# InterlockAdapter.net
KiCad netlist of a schematic drawn in EAGLE
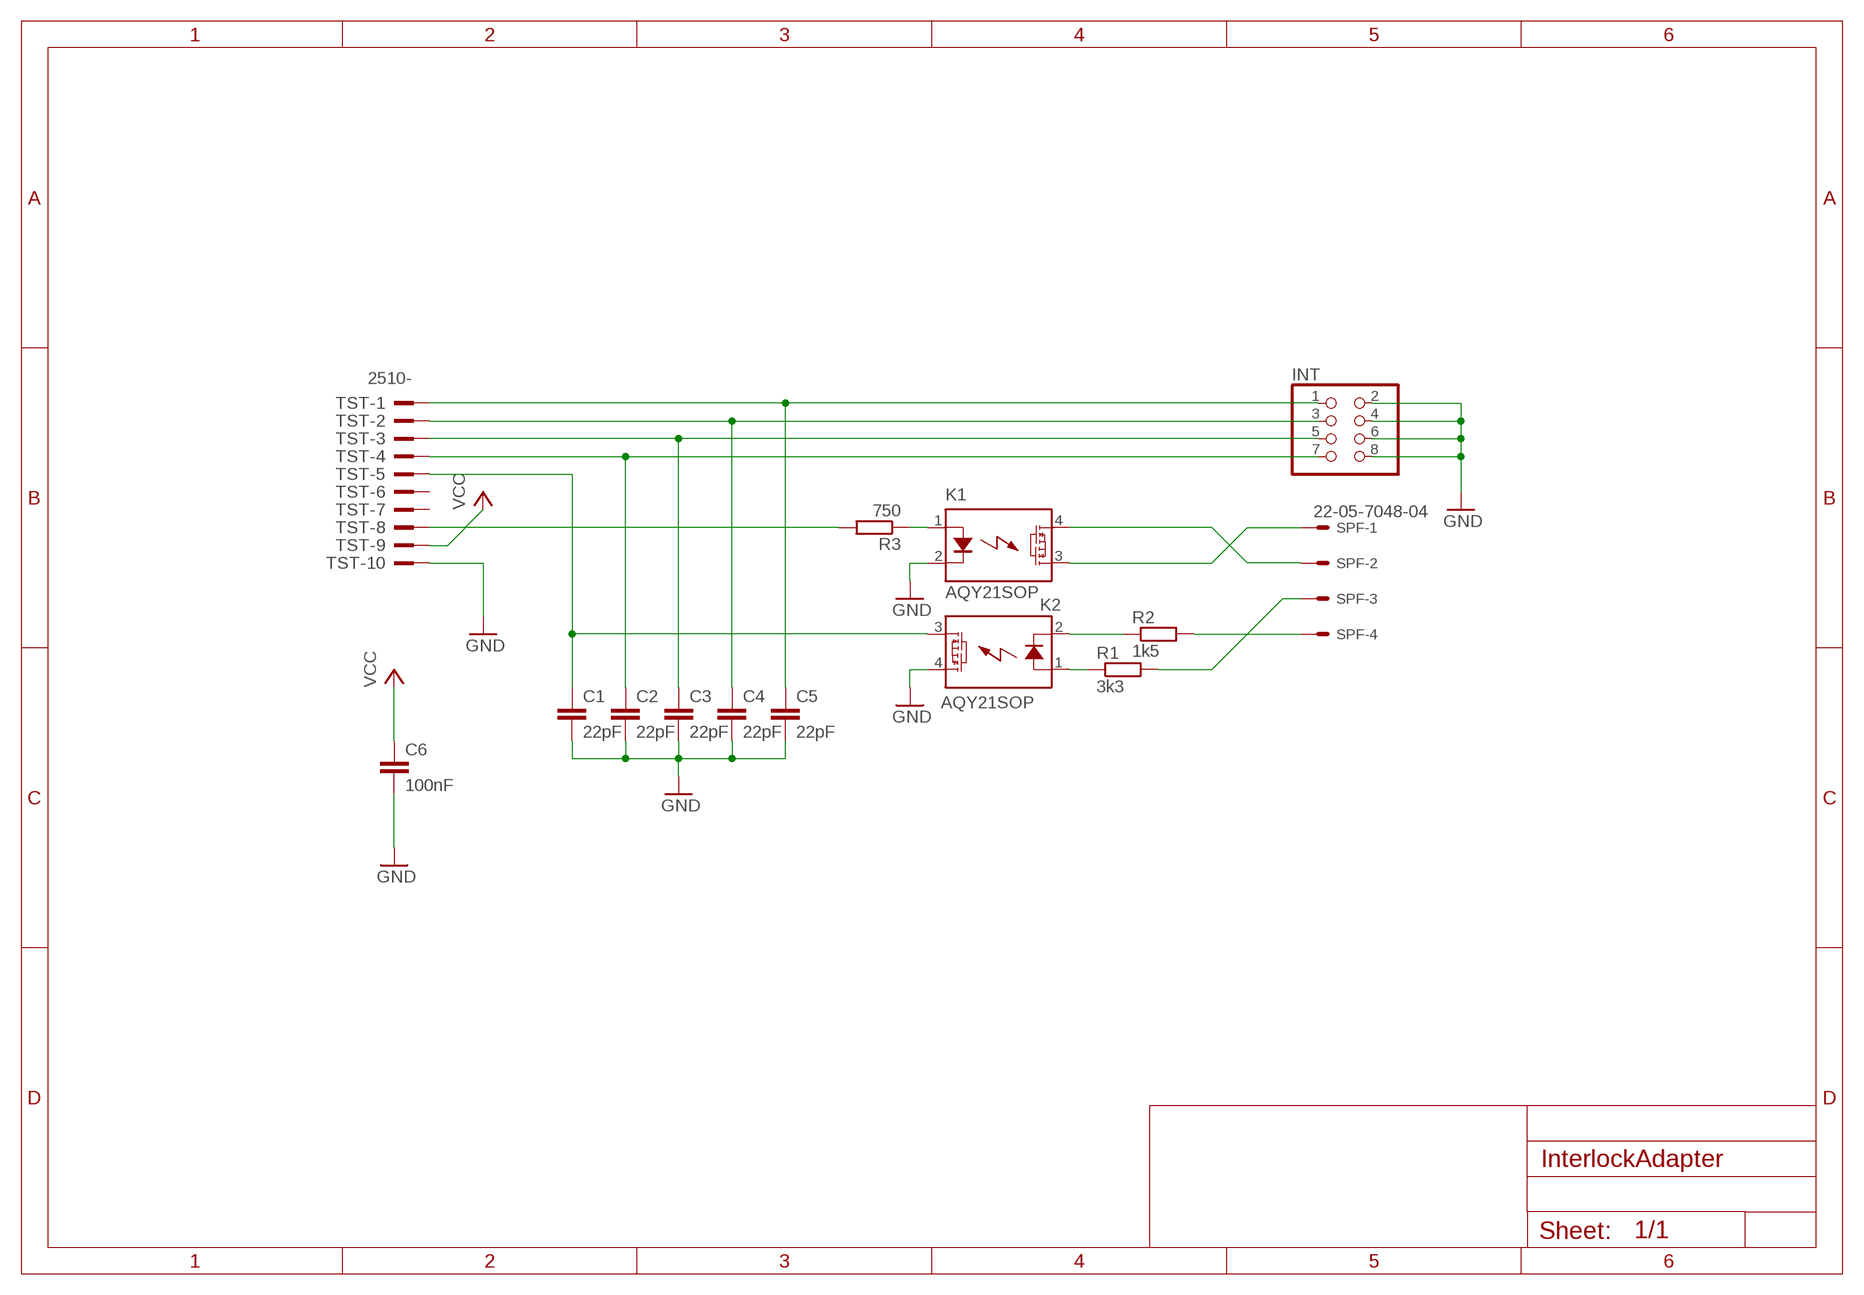
[diagram p0: schematic, sheet 1]

(export (version "E")
  (design (tool "Eeschema 10.0.6"))
  (components
    (comp (ref "C1")
      (value "22pF")
      (footprint "eagle-import:C1206K")
      (libsource (lib "eagle-import") (part "C-EUC1206K"))
    )
    (comp (ref "C2")
      (value "22pF")
      (footprint "eagle-import:C1206K")
      (libsource (lib "eagle-import") (part "C-EUC1206K"))
    )
    (comp (ref "C3")
      (value "22pF")
      (footprint "eagle-import:C1206K")
      (libsource (lib "eagle-import") (part "C-EUC1206K"))
    )
    (comp (ref "C4")
      (value "22pF")
      (footprint "eagle-import:C1206K")
      (libsource (lib "eagle-import") (part "C-EUC1206K"))
    )
    (comp (ref "C5")
      (value "22pF")
      (footprint "eagle-import:C1206K")
      (libsource (lib "eagle-import") (part "C-EUC1206K"))
    )
    (comp (ref "C6")
      (value "100nF")
      (footprint "eagle-import:C1206K")
      (libsource (lib "eagle-import") (part "C-EUC1206K"))
    )
    (comp (ref "INT")
      (value "PINHD-2X4/90")
      (footprint "eagle-import:2X04_90")
      (libsource (lib "eagle-import") (part "PINHD-2X4/90"))
    )
    (comp (ref "K1")
      (value "AQY21SOP")
      (footprint "eagle-import:SOP04")
      (libsource (lib "eagle-import") (part "AQYSOP21"))
    )
    (comp (ref "K2")
      (value "AQY21SOP")
      (footprint "eagle-import:SOP04")
      (libsource (lib "eagle-import") (part "AQYSOP21"))
    )
    (comp (ref "R1")
      (value "3k3")
      (footprint "eagle-import:R1206")
      (libsource (lib "eagle-import") (part "R-EU_R1206"))
    )
    (comp (ref "R2")
      (value "1k5")
      (footprint "eagle-import:R1206")
      (libsource (lib "eagle-import") (part "R-EU_R1206"))
    )
    (comp (ref "R3")
      (value "750")
      (footprint "eagle-import:R1206")
      (libsource (lib "eagle-import") (part "R-EU_R1206"))
    )
    (comp (ref "SPF")
      (value "22-05-7048-04")
      (footprint "eagle-import:7395-04")
      (libsource (lib "eagle-import") (part "22-?-0405-7048"))
    )
    (comp (ref "TST")
      (value "2510-")
      (footprint "eagle-import:PAK100_2500-10")
      (fields (field (name "MF") "3M") (field (name "MPN") "2510-6002UB"))
      (libsource (lib "eagle-import") (part "2510-"))
    )
  )
  (nets
    (net (code "1") (name "GND") (class "Default")
      (node (ref "C1") (pin "2") (pinfunction "2_2") (pintype "passive"))
      (node (ref "C2") (pin "2") (pinfunction "2_2") (pintype "passive"))
      (node (ref "C3") (pin "2") (pinfunction "2_2") (pintype "passive"))
      (node (ref "C4") (pin "2") (pinfunction "2_2") (pintype "passive"))
      (node (ref "C5") (pin "2") (pinfunction "2_2") (pintype "passive"))
      (node (ref "C6") (pin "2") (pinfunction "2_2") (pintype "passive"))
      (node (ref "INT") (pin "2") (pinfunction "2_2") (pintype "passive"))
      (node (ref "INT") (pin "4") (pinfunction "4_4") (pintype "passive"))
      (node (ref "INT") (pin "6") (pinfunction "6_6") (pintype "passive"))
      (node (ref "INT") (pin "8") (pinfunction "8_8") (pintype "passive"))
      (node (ref "K1") (pin "2") (pinfunction "K_2") (pintype "passive"))
      (node (ref "K2") (pin "4") (pinfunction "DS1_4") (pintype "passive"))
      (node (ref "TST") (pin "10") (pinfunction "KL_10") (pintype "passive"))
    )
    (net (code "2") (name "Net-(K1-A)") (class "Default")
      (node (ref "K1") (pin "1") (pinfunction "A_1") (pintype "passive"))
      (node (ref "R3") (pin "1") (pinfunction "1_1") (pintype "passive"))
    )
    (net (code "3") (name "Net-(K1-DS1)") (class "Default")
      (node (ref "K1") (pin "4") (pinfunction "DS1_4") (pintype "passive"))
      (node (ref "SPF") (pin "2") (pinfunction "S_2") (pintype "passive"))
    )
    (net (code "4") (name "Net-(K1-DS2)") (class "Default")
      (node (ref "K1") (pin "3") (pinfunction "DS2_3") (pintype "passive"))
      (node (ref "SPF") (pin "1") (pinfunction "S_1") (pintype "passive"))
    )
    (net (code "5") (name "Net-(K2-A)") (class "Default")
      (node (ref "K2") (pin "1") (pinfunction "A_1") (pintype "passive"))
      (node (ref "R1") (pin "1") (pinfunction "1_1") (pintype "passive"))
    )
    (net (code "6") (name "Net-(K2-DS2)") (class "Default")
      (node (ref "C1") (pin "1") (pinfunction "1_1") (pintype "passive"))
      (node (ref "K2") (pin "3") (pinfunction "DS2_3") (pintype "passive"))
      (node (ref "TST") (pin "5") (pinfunction "KL_5") (pintype "passive"))
    )
    (net (code "7") (name "Net-(K2-K)") (class "Default")
      (node (ref "K2") (pin "2") (pinfunction "K_2") (pintype "passive"))
      (node (ref "R2") (pin "1") (pinfunction "1_1") (pintype "passive"))
    )
    (net (code "8") (name "Net-(SPFC-S)") (class "Default")
      (node (ref "R1") (pin "2") (pinfunction "2_2") (pintype "passive"))
      (node (ref "SPF") (pin "3") (pinfunction "S_3") (pintype "passive"))
    )
    (net (code "9") (name "Net-(SPFD-S)") (class "Default")
      (node (ref "R2") (pin "2") (pinfunction "2_2") (pintype "passive"))
      (node (ref "SPF") (pin "4") (pinfunction "S_4") (pintype "passive"))
    )
    (net (code "10") (name "Net-(TSTA-KL)") (class "Default")
      (node (ref "C5") (pin "1") (pinfunction "1_1") (pintype "passive"))
      (node (ref "INT") (pin "1") (pinfunction "1_1") (pintype "passive"))
      (node (ref "TST") (pin "1") (pinfunction "KL_1") (pintype "passive"))
    )
    (net (code "11") (name "Net-(TSTC-KL)") (class "Default")
      (node (ref "C4") (pin "1") (pinfunction "1_1") (pintype "passive"))
      (node (ref "INT") (pin "3") (pinfunction "3_3") (pintype "passive"))
      (node (ref "TST") (pin "2") (pinfunction "KL_2") (pintype "passive"))
    )
    (net (code "12") (name "Net-(TSTD-KL)") (class "Default")
      (node (ref "C3") (pin "1") (pinfunction "1_1") (pintype "passive"))
      (node (ref "INT") (pin "5") (pinfunction "5_5") (pintype "passive"))
      (node (ref "TST") (pin "3") (pinfunction "KL_3") (pintype "passive"))
    )
    (net (code "13") (name "Net-(TSTE-KL)") (class "Default")
      (node (ref "C2") (pin "1") (pinfunction "1_1") (pintype "passive"))
      (node (ref "INT") (pin "7") (pinfunction "7_7") (pintype "passive"))
      (node (ref "TST") (pin "4") (pinfunction "KL_4") (pintype "passive"))
    )
    (net (code "14") (name "Net-(TSTI-KL)") (class "Default")
      (node (ref "R3") (pin "2") (pinfunction "2_2") (pintype "passive"))
      (node (ref "TST") (pin "8") (pinfunction "KL_8") (pintype "passive"))
    )
    (net (code "15") (name "VCC") (class "Default")
      (node (ref "C6") (pin "1") (pinfunction "1_1") (pintype "passive"))
      (node (ref "TST") (pin "9") (pinfunction "KL_9") (pintype "passive"))
    )
    (net (code "16") (name "unconnected-(TSTG-KL-Pad6)") (class "Default")
      (node (ref "TST") (pin "6") (pinfunction "KL_6") (pintype "passive"))
    )
    (net (code "17") (name "unconnected-(TSTH-KL-Pad7)") (class "Default")
      (node (ref "TST") (pin "7") (pinfunction "KL_7") (pintype "passive"))
    )
  )
)
